# combined_pressure_sensor_rev2.net
KiCad netlist of a schematic drawn in EAGLE
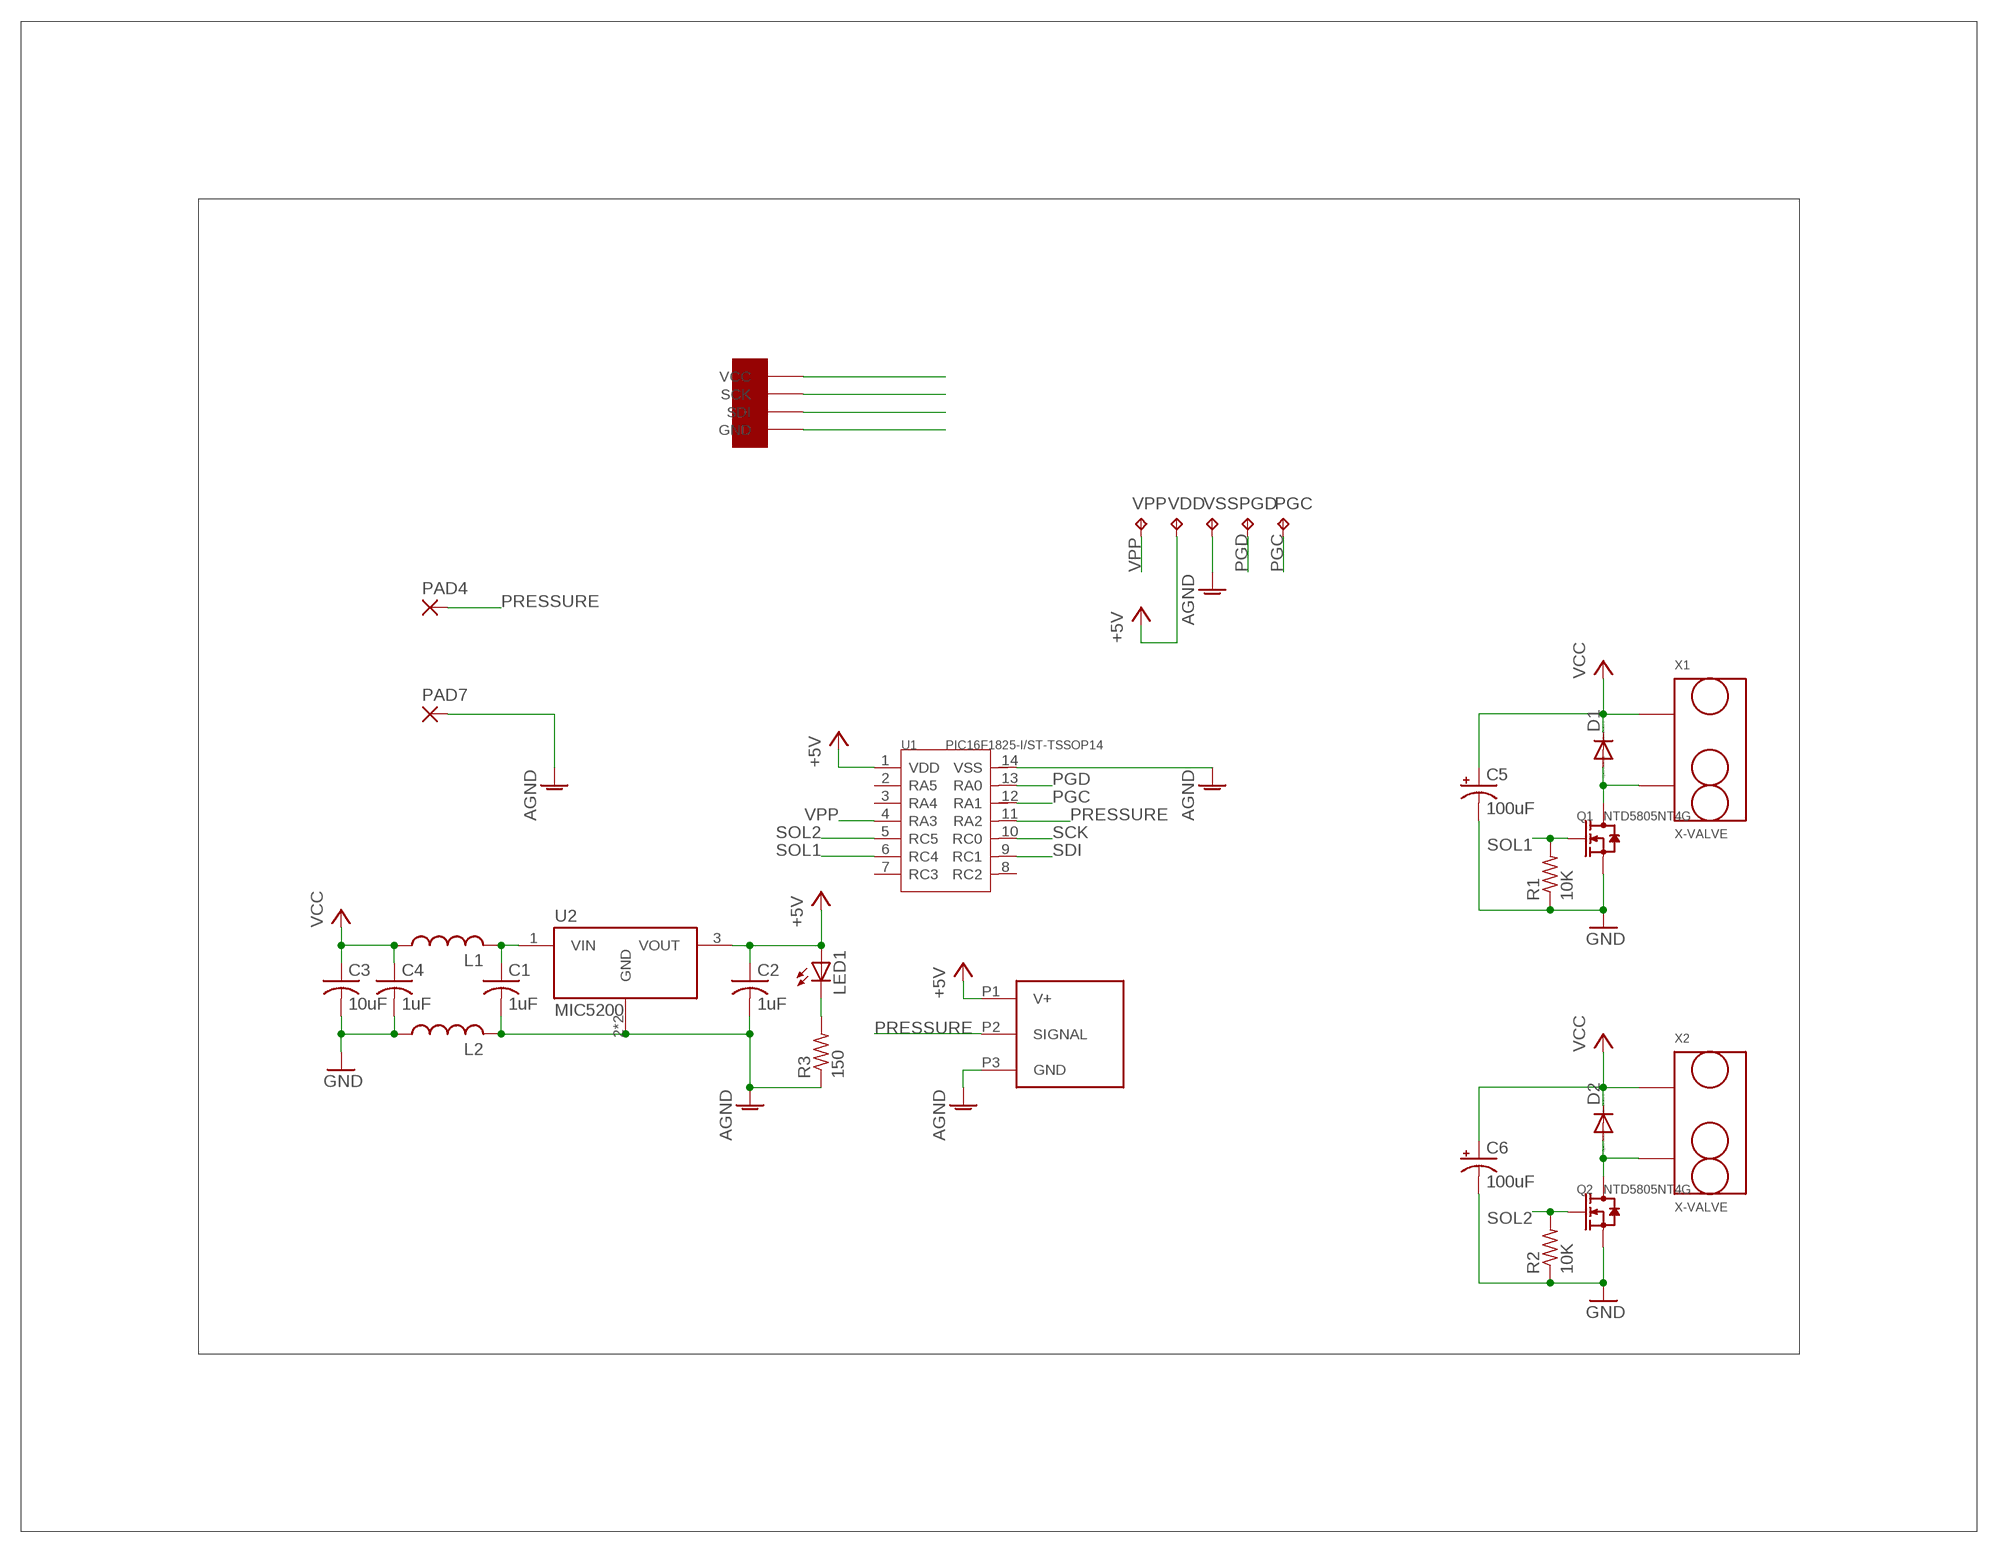
[diagram p0: schematic, sheet 1]

(export (version "E")
  (design (tool "Eeschema 10.0.6"))
  (components
    (comp (ref "C1")
      (value "1uF")
      (footprint "eagle-import:C0603")
      (libsource (lib "eagle-import") (part "C-USC0603"))
    )
    (comp (ref "C2")
      (value "1uF")
      (footprint "eagle-import:C0603")
      (libsource (lib "eagle-import") (part "C-USC0603"))
    )
    (comp (ref "C3")
      (value "10uF")
      (footprint "eagle-import:C1206")
      (libsource (lib "eagle-import") (part "C-USC1206"))
    )
    (comp (ref "C4")
      (value "1uF")
      (footprint "eagle-import:C0603")
      (libsource (lib "eagle-import") (part "C-USC0603"))
    )
    (comp (ref "C5")
      (value "100uF")
      (footprint "eagle-import:153CLV-0605")
      (libsource (lib "eagle-import") (part "CPOL-US153CLV-0605"))
    )
    (comp (ref "C6")
      (value "100uF")
      (footprint "eagle-import:153CLV-0605")
      (libsource (lib "eagle-import") (part "CPOL-US153CLV-0605"))
    )
    (comp (ref "D1")
      (value "DIODE-SOD523")
      (footprint "eagle-import:SOD523")
      (libsource (lib "eagle-import") (part "DIODE-SOD523"))
    )
    (comp (ref "D2")
      (value "DIODE-SOD523")
      (footprint "eagle-import:SOD523")
      (libsource (lib "eagle-import") (part "DIODE-SOD523"))
    )
    (comp (ref "L1")
      (value "L-USL1206")
      (footprint "eagle-import:L1206")
      (libsource (lib "eagle-import") (part "L-USL1206"))
    )
    (comp (ref "L2")
      (value "L-USL1206")
      (footprint "eagle-import:L1206")
      (libsource (lib "eagle-import") (part "L-USL1206"))
    )
    (comp (ref "LED1")
      (value "LEDCHIP-LED0603")
      (footprint "eagle-import:CHIP-LED0603")
      (libsource (lib "eagle-import") (part "LEDCHIP-LED0603"))
    )
    (comp (ref "PAD4")
      (value "SMD2")
      (footprint "eagle-import:SMD1,27-2,54")
      (libsource (lib "eagle-import") (part "SMD2"))
    )
    (comp (ref "PAD7")
      (value "SMD2")
      (footprint "eagle-import:SMD1,27-2,54")
      (libsource (lib "eagle-import") (part "SMD2"))
    )
    (comp (ref "PGC")
      (value "TPB1,27")
      (footprint "eagle-import:B1,27")
      (libsource (lib "eagle-import") (part "TPB1,27"))
    )
    (comp (ref "PGD")
      (value "TPB1,27")
      (footprint "eagle-import:B1,27")
      (libsource (lib "eagle-import") (part "TPB1,27"))
    )
    (comp (ref "Q1")
      (value "NTD5805NT4G")
      (footprint "eagle-import:DPAK")
      (libsource (lib "eagle-import") (part "SMD-MOSFET-HIGH-POWER-N-CH-40V-51A-NTD5805NT4G(DPAK)"))
    )
    (comp (ref "Q2")
      (value "NTD5805NT4G")
      (footprint "eagle-import:DPAK")
      (libsource (lib "eagle-import") (part "SMD-MOSFET-HIGH-POWER-N-CH-40V-51A-NTD5805NT4G(DPAK)"))
    )
    (comp (ref "R1")
      (value "10K")
      (footprint "eagle-import:R0603")
      (libsource (lib "eagle-import") (part "R-US_R0603"))
    )
    (comp (ref "R2")
      (value "10K")
      (footprint "eagle-import:R0603")
      (libsource (lib "eagle-import") (part "R-US_R0603"))
    )
    (comp (ref "R3")
      (value "150")
      (footprint "eagle-import:R0603")
      (libsource (lib "eagle-import") (part "R-US_R0603"))
    )
    (comp (ref "U$1")
      (value "PICOBLADE4POS1.25MMRIGHTANGLESURFACE")
      (footprint "eagle-import:PICOBLADE4POSMALEHEADER")
      (libsource (lib "eagle-import") (part "PICOBLADE4POS1.25MMRIGHTANGLESURFACE"))
    )
    (comp (ref "U$3")
      (value "ASDX")
      (footprint "eagle-import:ASDX")
      (libsource (lib "eagle-import") (part "ASDX"))
    )
    (comp (ref "U1")
      (value "PIC16F1825-I/ST-TSSOP14")
      (footprint "eagle-import:TSSOP14-0.65-5X4.4MM")
      (fields (field (name "MPN") "PIC16F1825-I/ST"))
      (libsource (lib "eagle-import") (part "MCU-PIC16F1825-I/ST(TSSOP14)"))
    )
    (comp (ref "U2")
      (value "MIC5200")
      (footprint "eagle-import:SOT223")
      (libsource (lib "eagle-import") (part "MIC5200"))
    )
    (comp (ref "VDD")
      (value "TPB1,27")
      (footprint "eagle-import:B1,27")
      (libsource (lib "eagle-import") (part "TPB1,27"))
    )
    (comp (ref "VPP")
      (value "TPB1,27")
      (footprint "eagle-import:B1,27")
      (libsource (lib "eagle-import") (part "TPB1,27"))
    )
    (comp (ref "VSS")
      (value "TPB1,27")
      (footprint "eagle-import:B1,27")
      (libsource (lib "eagle-import") (part "TPB1,27"))
    )
    (comp (ref "X1")
      (value "X-VALVE")
      (footprint "eagle-import:X-VALVE")
      (libsource (lib "eagle-import") (part "X-VALVE"))
    )
    (comp (ref "X2")
      (value "X-VALVE")
      (footprint "eagle-import:X-VALVE")
      (libsource (lib "eagle-import") (part "X-VALVE"))
    )
  )
  (nets
    (net (code "1") (name "+5V") (class "Default")
      (node (ref "C2") (pin "1") (pinfunction "1_1") (pintype "passive"))
      (node (ref "LED1") (pin "A") (pinfunction "A_A") (pintype "passive"))
      (node (ref "U$3") (pin "P1") (pinfunction "V+_P1") (pintype "bidirectional"))
      (node (ref "U1") (pin "1") (pinfunction "VDD_1") (pintype "bidirectional"))
      (node (ref "U2") (pin "3") (pinfunction "VOUT_3") (pintype "bidirectional"))
      (node (ref "VDD") (pin "TP") (pinfunction "TP_TP") (pintype "input"))
    )
    (net (code "2") (name "/PGC") (class "Default")
      (node (ref "PGC") (pin "TP") (pinfunction "TP_TP") (pintype "input"))
      (node (ref "U1") (pin "12") (pinfunction "RA1_12") (pintype "bidirectional"))
    )
    (net (code "3") (name "/PGD") (class "Default")
      (node (ref "PGD") (pin "TP") (pinfunction "TP_TP") (pintype "input"))
      (node (ref "U1") (pin "13") (pinfunction "RA0_13") (pintype "bidirectional"))
    )
    (net (code "4") (name "/PRESSURE") (class "Default")
      (node (ref "PAD4") (pin "1") (pinfunction "P_1") (pintype "passive"))
      (node (ref "U$3") (pin "P2") (pinfunction "SIGNAL_P2") (pintype "bidirectional"))
      (node (ref "U1") (pin "11") (pinfunction "RA2_11") (pintype "bidirectional"))
    )
    (net (code "5") (name "/SCK") (class "Default")
      (node (ref "U$1") (pin "SCK") (pinfunction "SCK_SCK") (pintype "bidirectional"))
      (node (ref "U1") (pin "10") (pinfunction "RC0_10") (pintype "bidirectional"))
    )
    (net (code "6") (name "/SDI") (class "Default")
      (node (ref "U$1") (pin "SDI") (pinfunction "SDI_SDI") (pintype "bidirectional"))
      (node (ref "U1") (pin "9") (pinfunction "RC1_9") (pintype "bidirectional"))
    )
    (net (code "7") (name "/SOL1") (class "Default")
      (node (ref "Q1") (pin "1") (pinfunction "G_1") (pintype "passive"))
      (node (ref "R1") (pin "2") (pinfunction "2_2") (pintype "passive"))
      (node (ref "U1") (pin "6") (pinfunction "RC4_6") (pintype "bidirectional"))
    )
    (net (code "8") (name "/SOL2") (class "Default")
      (node (ref "Q2") (pin "1") (pinfunction "G_1") (pintype "passive"))
      (node (ref "R2") (pin "2") (pinfunction "2_2") (pintype "passive"))
      (node (ref "U1") (pin "5") (pinfunction "RC5_5") (pintype "bidirectional"))
    )
    (net (code "9") (name "/VPP") (class "Default")
      (node (ref "U1") (pin "4") (pinfunction "RA3_4") (pintype "bidirectional"))
      (node (ref "VPP") (pin "TP") (pinfunction "TP_TP") (pintype "input"))
    )
    (net (code "10") (name "AGND") (class "Default")
      (node (ref "C1") (pin "2") (pinfunction "2_2") (pintype "passive"))
      (node (ref "C2") (pin "2") (pinfunction "2_2") (pintype "passive"))
      (node (ref "L2") (pin "2") (pinfunction "2_2") (pintype "passive"))
      (node (ref "PAD7") (pin "1") (pinfunction "P_1") (pintype "passive"))
      (node (ref "R3") (pin "1") (pinfunction "1_1") (pintype "passive"))
      (node (ref "U$3") (pin "P3") (pinfunction "GND_P3") (pintype "bidirectional"))
      (node (ref "U1") (pin "14") (pinfunction "VSS_14") (pintype "bidirectional"))
      (node (ref "U2") (pin "2") (pinfunction "GND_2") (pintype "bidirectional"))
      (node (ref "U2") (pin "4") (pinfunction "GND_4") (pintype "bidirectional"))
      (node (ref "VSS") (pin "TP") (pinfunction "TP_TP") (pintype "input"))
    )
    (net (code "11") (name "GND") (class "Default")
      (node (ref "C3") (pin "2") (pinfunction "2_2") (pintype "passive"))
      (node (ref "C4") (pin "2") (pinfunction "2_2") (pintype "passive"))
      (node (ref "C5") (pin "-") (pinfunction "-_-") (pintype "passive"))
      (node (ref "C6") (pin "-") (pinfunction "-_-") (pintype "passive"))
      (node (ref "L2") (pin "1") (pinfunction "1_1") (pintype "passive"))
      (node (ref "Q1") (pin "2") (pinfunction "S_2") (pintype "passive"))
      (node (ref "Q2") (pin "2") (pinfunction "S_2") (pintype "passive"))
      (node (ref "R1") (pin "1") (pinfunction "1_1") (pintype "passive"))
      (node (ref "R2") (pin "1") (pinfunction "1_1") (pintype "passive"))
      (node (ref "U$1") (pin "GND") (pinfunction "GND_GND") (pintype "bidirectional"))
    )
    (net (code "12") (name "Net-(LED1-PadC)") (class "Default")
      (node (ref "LED1") (pin "C") (pinfunction "C_C") (pintype "passive"))
      (node (ref "R3") (pin "2") (pinfunction "2_2") (pintype "passive"))
    )
    (net (code "13") (name "Net-(Q1-D)") (class "Default")
      (node (ref "D1") (pin "A") (pinfunction "A_A") (pintype "passive"))
      (node (ref "Q1") (pin "3") (pinfunction "D_3") (pintype "passive"))
      (node (ref "X1") (pin "P$2") (pinfunction "P$2_P$2") (pintype "bidirectional"))
    )
    (net (code "14") (name "Net-(Q2-D)") (class "Default")
      (node (ref "D2") (pin "A") (pinfunction "A_A") (pintype "passive"))
      (node (ref "Q2") (pin "3") (pinfunction "D_3") (pintype "passive"))
      (node (ref "X2") (pin "P$2") (pinfunction "P$2_P$2") (pintype "bidirectional"))
    )
    (net (code "15") (name "Net-(U2-VIN)") (class "Default")
      (node (ref "C1") (pin "1") (pinfunction "1_1") (pintype "passive"))
      (node (ref "L1") (pin "2") (pinfunction "2_2") (pintype "passive"))
      (node (ref "U2") (pin "1") (pinfunction "VIN_1") (pintype "bidirectional"))
    )
    (net (code "16") (name "VCC") (class "Default")
      (node (ref "C3") (pin "1") (pinfunction "1_1") (pintype "passive"))
      (node (ref "C4") (pin "1") (pinfunction "1_1") (pintype "passive"))
      (node (ref "C5") (pin "+") (pinfunction "+_+") (pintype "passive"))
      (node (ref "C6") (pin "+") (pinfunction "+_+") (pintype "passive"))
      (node (ref "D1") (pin "C") (pinfunction "C_C") (pintype "passive"))
      (node (ref "D2") (pin "C") (pinfunction "C_C") (pintype "passive"))
      (node (ref "L1") (pin "1") (pinfunction "1_1") (pintype "passive"))
      (node (ref "U$1") (pin "VCC") (pinfunction "VCC_VCC") (pintype "bidirectional"))
      (node (ref "X1") (pin "P$1") (pinfunction "P$1_P$1") (pintype "bidirectional"))
      (node (ref "X2") (pin "P$1") (pinfunction "P$1_P$1") (pintype "bidirectional"))
    )
    (net (code "17") (name "unconnected-(U1-RA4-Pad3)") (class "Default")
      (node (ref "U1") (pin "3") (pinfunction "RA4_3") (pintype "bidirectional"))
    )
    (net (code "18") (name "unconnected-(U1-RA5-Pad2)") (class "Default")
      (node (ref "U1") (pin "2") (pinfunction "RA5_2") (pintype "bidirectional"))
    )
    (net (code "19") (name "unconnected-(U1-RC2-Pad8)") (class "Default")
      (node (ref "U1") (pin "8") (pinfunction "RC2_8") (pintype "bidirectional"))
    )
    (net (code "20") (name "unconnected-(U1-RC3-Pad7)") (class "Default")
      (node (ref "U1") (pin "7") (pinfunction "RC3_7") (pintype "bidirectional"))
    )
  )
)
